# Level_Translation.net
KiCad netlist of a schematic drawn in Altium Designer
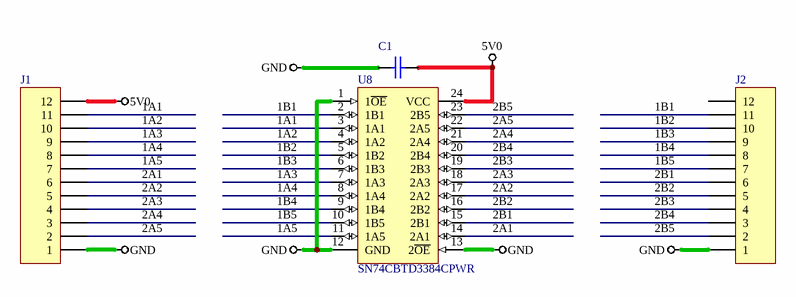
[diagram p0: Level_Translation.SchDoc]

(export (version "E")
  (design (tool "Eeschema 10.0.6"))
  (components
    (comp (ref "C1")
      (value "CAP 100nF 16V 0805(2012)")
      (footprint "CAPC0805(2012)100_M")
      (description "CAP 100nF 16V Â±5% 0805 (2012 Metric) Thickness 1mm SMD")
      (fields (field (name "TOLERANCE") "Â±5%"))
      (libsource (lib "Altium Content Vault") (part "CAP"))
    )
    (comp (ref "J1")
      (value "Header 12")
      (footprint "HDR1X12")
      (description "Header, 12-Pin")
      (fields (field (name "PUBLISHER") "Altium Limited"))
      (libsource (lib "Miscellaneous Connectors") (part "Header 12"))
    )
    (comp (ref "J2")
      (value "Header 12")
      (footprint "HDR1X12")
      (description "Header, 12-Pin")
      (fields (field (name "PUBLISHER") "Altium Limited"))
      (libsource (lib "") (part "Header 12_1"))
    )
    (comp (ref "U8")
      (value "SN74CBTD3384CPWR")
      (footprint "TSOP65P620X120-24N")
      (description "10-BIT FET BUS SWITCH WITH LEVEL SHIFTING")
      (fields (field (name "MANUFACTURER") "Texas Instruments"))
      (libsource (lib "SN74CBTD3384CPWR") (part "SN74CBTD3384CPWR"))
    )
  )
  (nets
    (net (code "1") (name "/1A1") (class "Default")
      (node (ref "J1") (pin "11") (pinfunction "11_11") (pintype "passive"))
      (node (ref "U8") (pin "3") (pinfunction "1A1_3") (pintype "bidirectional"))
    )
    (net (code "2") (name "/1A2") (class "Default")
      (node (ref "J1") (pin "10") (pinfunction "10_10") (pintype "passive"))
      (node (ref "U8") (pin "4") (pinfunction "1A2_4") (pintype "bidirectional"))
    )
    (net (code "3") (name "/1A3") (class "Default")
      (node (ref "J1") (pin "9") (pinfunction "9_9") (pintype "passive"))
      (node (ref "U8") (pin "7") (pinfunction "1A3_7") (pintype "bidirectional"))
    )
    (net (code "4") (name "/1A4") (class "Default")
      (node (ref "J1") (pin "8") (pinfunction "8_8") (pintype "passive"))
      (node (ref "U8") (pin "8") (pinfunction "1A4_8") (pintype "bidirectional"))
    )
    (net (code "5") (name "/1A5") (class "Default")
      (node (ref "J1") (pin "7") (pinfunction "7_7") (pintype "passive"))
      (node (ref "U8") (pin "11") (pinfunction "1A5_11") (pintype "bidirectional"))
    )
    (net (code "6") (name "/1B1") (class "Default")
      (node (ref "J2") (pin "11") (pinfunction "11_11") (pintype "passive"))
      (node (ref "U8") (pin "2") (pinfunction "1B1_2") (pintype "bidirectional"))
    )
    (net (code "7") (name "/1B2") (class "Default")
      (node (ref "J2") (pin "10") (pinfunction "10_10") (pintype "passive"))
      (node (ref "U8") (pin "5") (pinfunction "1B2_5") (pintype "bidirectional"))
    )
    (net (code "8") (name "/1B3") (class "Default")
      (node (ref "J2") (pin "9") (pinfunction "9_9") (pintype "passive"))
      (node (ref "U8") (pin "6") (pinfunction "1B3_6") (pintype "bidirectional"))
    )
    (net (code "9") (name "/1B4") (class "Default")
      (node (ref "J2") (pin "8") (pinfunction "8_8") (pintype "passive"))
      (node (ref "U8") (pin "9") (pinfunction "1B4_9") (pintype "bidirectional"))
    )
    (net (code "10") (name "/1B5") (class "Default")
      (node (ref "J2") (pin "7") (pinfunction "7_7") (pintype "passive"))
      (node (ref "U8") (pin "10") (pinfunction "1B5_10") (pintype "bidirectional"))
    )
    (net (code "11") (name "/2A1") (class "Default")
      (node (ref "J1") (pin "6") (pinfunction "6_6") (pintype "passive"))
      (node (ref "U8") (pin "14") (pinfunction "2A1_14") (pintype "bidirectional"))
    )
    (net (code "12") (name "/2A2") (class "Default")
      (node (ref "J1") (pin "5") (pinfunction "5_5") (pintype "passive"))
      (node (ref "U8") (pin "17") (pinfunction "2A2_17") (pintype "bidirectional"))
    )
    (net (code "13") (name "/2A3") (class "Default")
      (node (ref "J1") (pin "4") (pinfunction "4_4") (pintype "passive"))
      (node (ref "U8") (pin "18") (pinfunction "2A3_18") (pintype "bidirectional"))
    )
    (net (code "14") (name "/2A4") (class "Default")
      (node (ref "J1") (pin "3") (pinfunction "3_3") (pintype "passive"))
      (node (ref "U8") (pin "21") (pinfunction "2A4_21") (pintype "bidirectional"))
    )
    (net (code "15") (name "/2A5") (class "Default")
      (node (ref "J1") (pin "2") (pinfunction "2_2") (pintype "passive"))
      (node (ref "U8") (pin "22") (pinfunction "2A5_22") (pintype "bidirectional"))
    )
    (net (code "16") (name "/2B1") (class "Default")
      (node (ref "J2") (pin "6") (pinfunction "6_6") (pintype "passive"))
      (node (ref "U8") (pin "15") (pinfunction "2B1_15") (pintype "bidirectional"))
    )
    (net (code "17") (name "/2B2") (class "Default")
      (node (ref "J2") (pin "5") (pinfunction "5_5") (pintype "passive"))
      (node (ref "U8") (pin "16") (pinfunction "2B2_16") (pintype "bidirectional"))
    )
    (net (code "18") (name "/2B3") (class "Default")
      (node (ref "J2") (pin "4") (pinfunction "4_4") (pintype "passive"))
      (node (ref "U8") (pin "19") (pinfunction "2B3_19") (pintype "bidirectional"))
    )
    (net (code "19") (name "/2B4") (class "Default")
      (node (ref "J2") (pin "3") (pinfunction "3_3") (pintype "passive"))
      (node (ref "U8") (pin "20") (pinfunction "2B4_20") (pintype "bidirectional"))
    )
    (net (code "20") (name "/2B5") (class "Default")
      (node (ref "J2") (pin "2") (pinfunction "2_2") (pintype "passive"))
      (node (ref "U8") (pin "23") (pinfunction "2B5_23") (pintype "bidirectional"))
    )
    (net (code "21") (name "5V0") (class "Default")
      (node (ref "C1") (pin "2") (pinfunction "2_2") (pintype "passive"))
      (node (ref "J1") (pin "12") (pinfunction "12_12") (pintype "passive"))
      (node (ref "U8") (pin "24") (pinfunction "VCC_24") (pintype "passive"))
    )
    (net (code "22") (name "GND") (class "Default")
      (node (ref "C1") (pin "1") (pinfunction "1_1") (pintype "passive"))
      (node (ref "J1") (pin "1") (pinfunction "1_1") (pintype "passive"))
      (node (ref "J2") (pin "1") (pinfunction "1_1") (pintype "passive"))
      (node (ref "U8") (pin "1") (pinfunction "1~{OE}_1") (pintype "input"))
      (node (ref "U8") (pin "12") (pinfunction "GND_12") (pintype "passive"))
      (node (ref "U8") (pin "13") (pinfunction "2~{OE}_13") (pintype "input"))
    )
    (net (code "23") (name "unconnected-(J2-Pad12)") (class "Default")
      (node (ref "J2") (pin "12") (pinfunction "12_12") (pintype "passive"))
    )
  )
)
